# arduino_SCH.net
KiCad netlist of a schematic drawn in Altium Designer
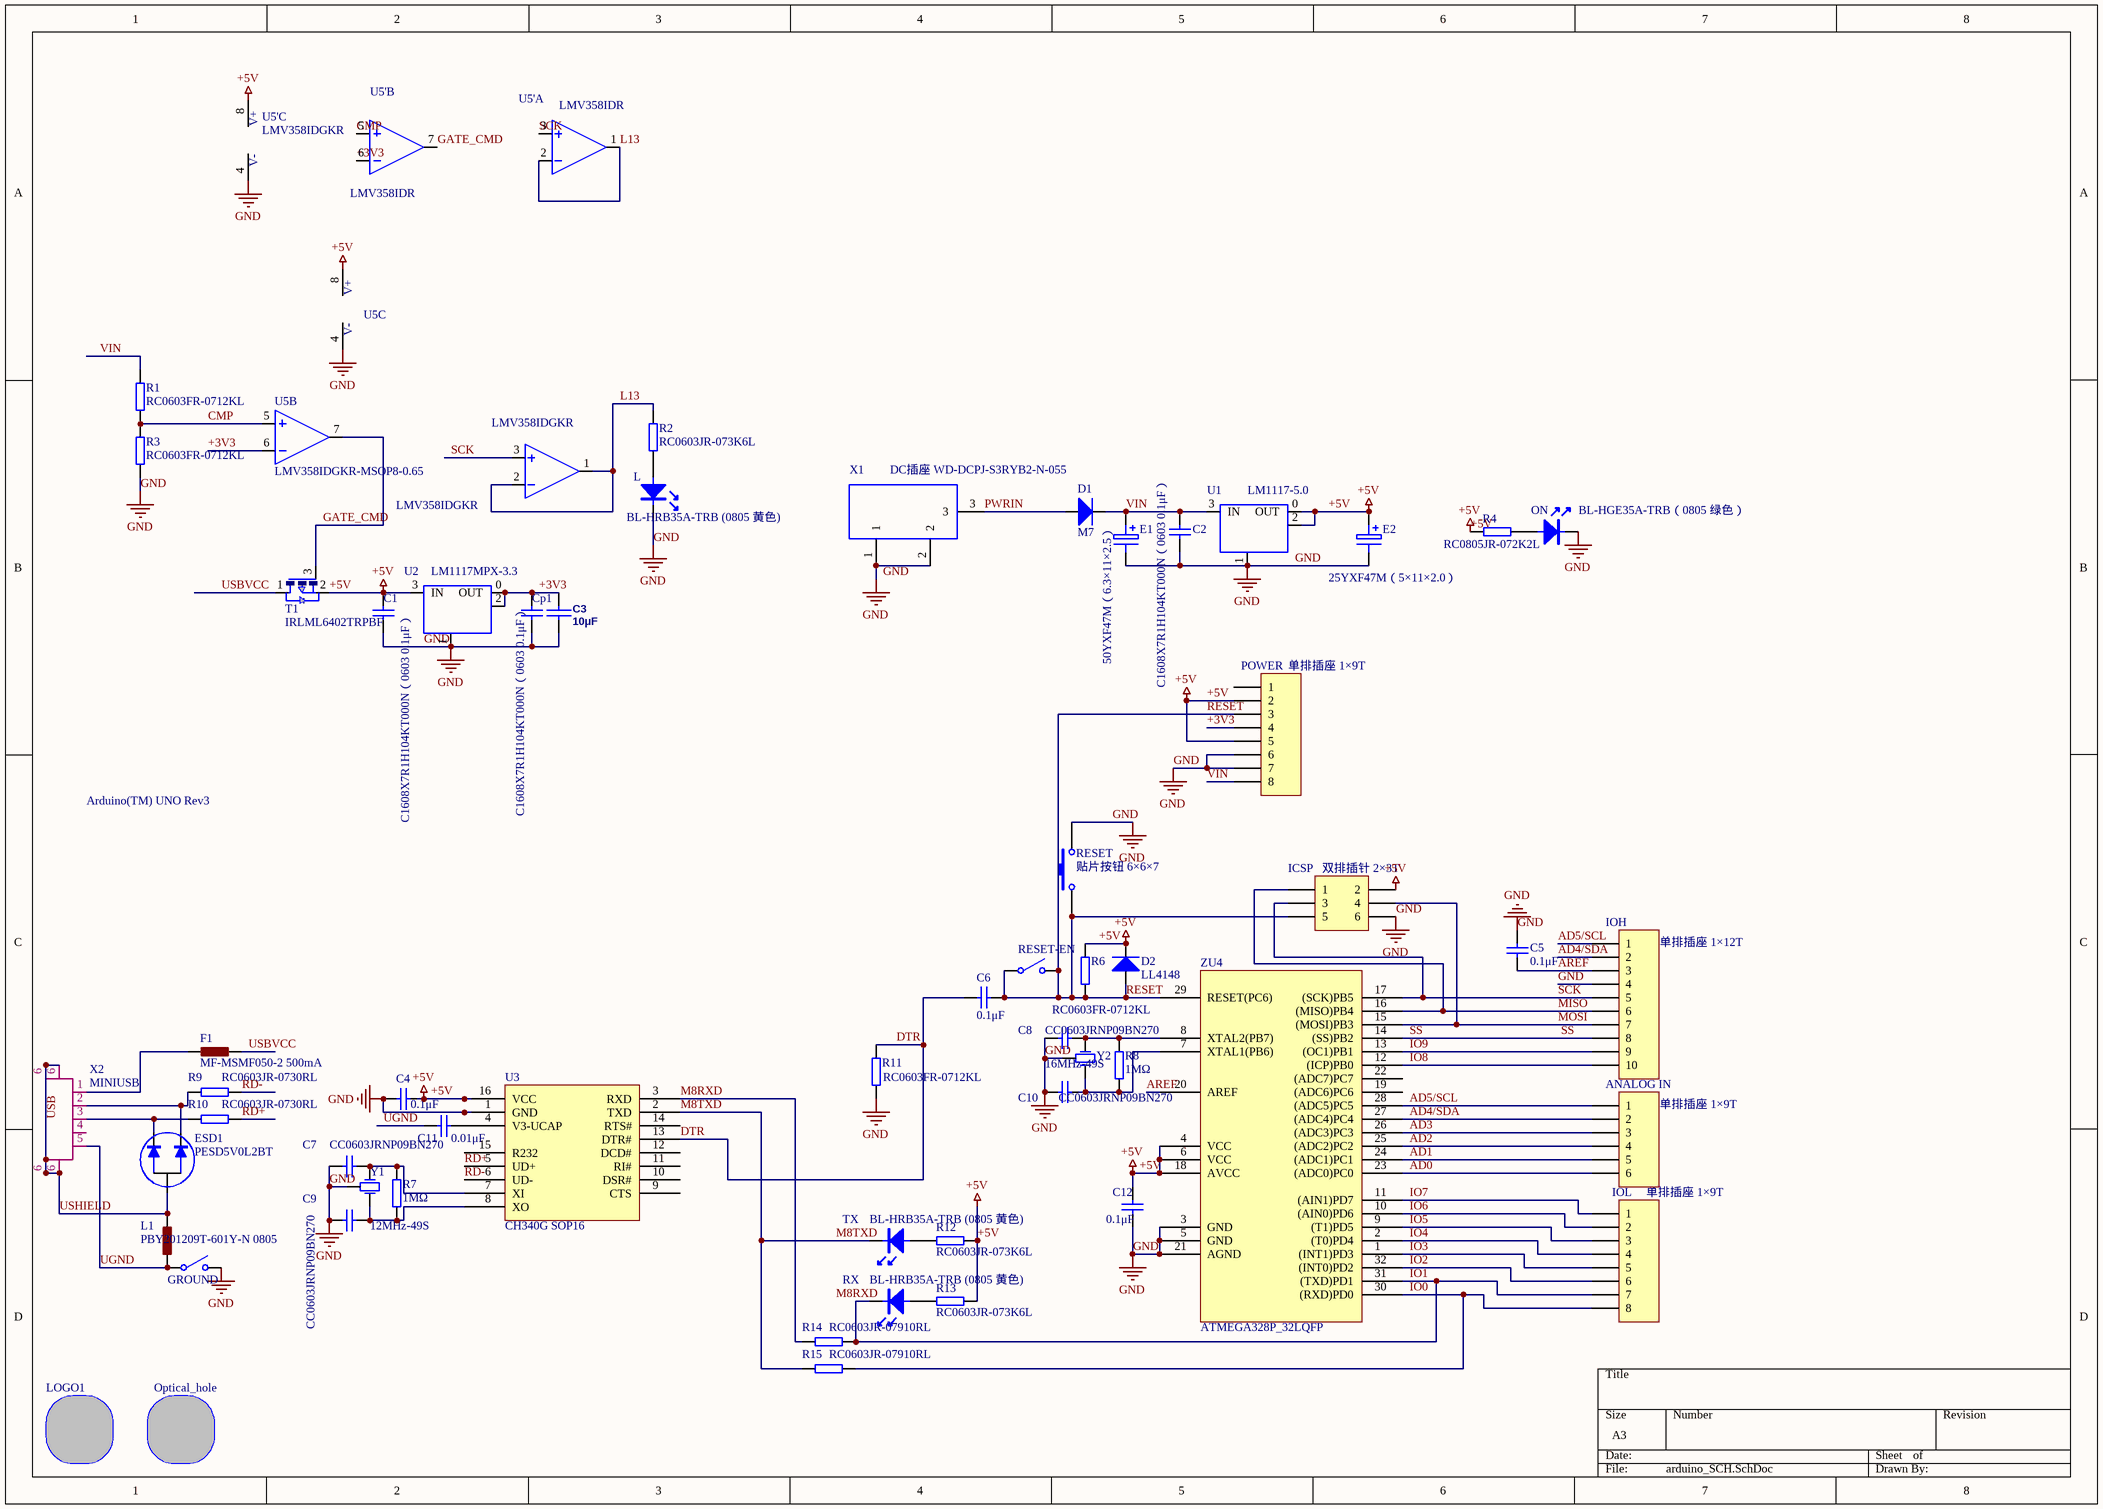
[diagram p0: arduino_SCH.SchDoc]

(export (version "E")
  (design (tool "Eeschema 10.0.6"))
  (components
    (comp (ref "ANALOG IN")
      (value "单排插座 1×9T")
      (footprint "HDR1X6Z")
      (description "Header, 6-Pin")
      (fields (field (name "PUBLISHER") "Altium Limited"))
      (libsource (lib "Miscellaneous Connectors") (part "Header 6"))
    )
    (comp (ref "C1")
      (value "C1608X7R1H104KT000N（0603 0.1μF）")
      (footprint "0603C")
      (description "Capacitor")
      (fields (field (name "PUBLISHER") "Altium Limited"))
      (libsource (lib "*") (part "Cap"))
    )
    (comp (ref "C2")
      (value "C1608X7R1H104KT000N（0603 0.1μF）")
      (footprint "0603C")
      (description "Capacitor")
      (fields (field (name "PUBLISHER") "Altium Limited"))
      (libsource (lib "Miscellaneous Devices") (part "Cap"))
    )
    (comp (ref "C3")
      (value "10μF")
      (footprint "1206C")
      (description "Capacitor")
      (libsource (lib "*") (part "CAP"))
    )
    (comp (ref "C4")
      (value "0.1μF")
      (footprint "0603C")
      (description "Capacitor")
      (fields (field (name "PUBLISHER") "Altium Limited"))
      (libsource (lib "Miscellaneous Devices") (part "Cap"))
    )
    (comp (ref "C5")
      (value "0.1μF")
      (footprint "0603C")
      (description "Capacitor")
      (fields (field (name "PUBLISHER") "Altium Limited"))
      (libsource (lib "Miscellaneous Devices") (part "Cap"))
    )
    (comp (ref "C6")
      (value "0.1μF")
      (footprint "0603C")
      (description "Capacitor")
      (fields (field (name "PUBLISHER") "Altium Limited"))
      (libsource (lib "Miscellaneous Devices") (part "Cap"))
    )
    (comp (ref "C7")
      (value "CC0603JRNP09BN270")
      (footprint "0603C")
      (description "Capacitor")
      (fields (field (name "PUBLISHER") "Altium Limited"))
      (libsource (lib "Miscellaneous Devices") (part "Cap"))
    )
    (comp (ref "C8")
      (value "CC0603JRNP09BN270")
      (footprint "0603C")
      (description "Capacitor")
      (fields (field (name "PUBLISHER") "Altium Limited"))
      (libsource (lib "Miscellaneous Devices") (part "Cap"))
    )
    (comp (ref "C9")
      (value "CC0603JRNP09BN270")
      (footprint "0603C")
      (description "Capacitor")
      (fields (field (name "PUBLISHER") "Altium Limited"))
      (libsource (lib "Miscellaneous Devices") (part "Cap"))
    )
    (comp (ref "C10")
      (value "CC0603JRNP09BN270")
      (footprint "0603C")
      (description "Capacitor")
      (fields (field (name "PUBLISHER") "Altium Limited"))
      (libsource (lib "Miscellaneous Devices") (part "Cap"))
    )
    (comp (ref "C11")
      (value "0.01μF")
      (footprint "0603C")
      (description "Capacitor")
      (fields (field (name "PUBLISHER") "Altium Limited"))
      (libsource (lib "Miscellaneous Devices") (part "Cap"))
    )
    (comp (ref "C12")
      (value "0.1μF")
      (footprint "0603C")
      (description "Capacitor")
      (fields (field (name "PUBLISHER") "Altium Limited"))
      (libsource (lib "Miscellaneous Devices") (part "Cap"))
    )
    (comp (ref "Cp1")
      (value "C1608X7R1H104KT000N（0603 0.1μF）")
      (footprint "0603C")
      (description "Capacitor")
      (fields (field (name "PUBLISHER") "Altium Limited"))
      (libsource (lib "*") (part "Cap"))
    )
    (comp (ref "D1")
      (value "M7")
      (footprint "M7")
      (description "D")
      (libsource (lib "Miscellaneous Devices") (part "M7"))
    )
    (comp (ref "D2")
      (value "LL4148")
      (footprint "D1206")
      (description "D")
      (libsource (lib "Miscellaneous Devices") (part "M7"))
    )
    (comp (ref "E1")
      (value "50YXF47M（6.3×11×2.5）")
      (footprint "RB 6.3×11×2.5")
      (libsource (lib "Miscellaneous Devices") (part "E"))
    )
    (comp (ref "E2")
      (value "25YXF47M（5×11×2.0）")
      (footprint "RB 6.3×11×2.5")
      (libsource (lib "Miscellaneous Devices") (part "E"))
    )
    (comp (ref "ESD1")
      (value "PESD5V0L2BT")
      (footprint "SOT-23")
      (libsource (lib "Miscellaneous Devices") (part "ESD1"))
    )
    (comp (ref "F1")
      (value "MF-MSMF050-2 500mA")
      (footprint "L1206")
      (description "BLM21")
      (libsource (lib "") (part "L_1"))
    )
    (comp (ref "GROUND")
      (value "~")
      (footprint "0101")
      (description "Single-Pole, Single-Throw Switch")
      (fields (field (name "PUBLISHER") "Altium Limited"))
      (libsource (lib "Miscellaneous Devices") (part "SW-SPST"))
    )
    (comp (ref "ICSP")
      (value "双排插针 2×3T")
      (footprint "HDR2X3")
      (description "Header, 3-Pin, Dual row")
      (fields (field (name "PUBLISHER") "Altium Limited"))
      (libsource (lib "Miscellaneous Connectors") (part "Header 3X2"))
    )
    (comp (ref "IOH")
      (value "单排插座 1×12T")
      (footprint "HDR1X10Z")
      (description "Header, 10-Pin")
      (fields (field (name "PUBLISHER") "Altium Limited"))
      (libsource (lib "Miscellaneous Connectors") (part "Header 10"))
    )
    (comp (ref "IOL")
      (value "单排插座 1×9T")
      (footprint "HDR1X8Z")
      (description "Header, 8-Pin")
      (fields (field (name "PUBLISHER") "Altium Limited"))
      (libsource (lib "Miscellaneous Connectors") (part "Header 8"))
    )
    (comp (ref "L")
      (value "BL-HRB35A-TRB (0805 黄色)")
      (footprint "LED0805-Y")
      (libsource (lib "Miscellaneous Devices") (part "LED"))
    )
    (comp (ref "L1")
      (value "PBY201209T-601Y-N 0805")
      (footprint "L0805")
      (description "BLM21")
      (libsource (lib "Miscellaneous Devices") (part "L"))
    )
    (comp (ref "LOGO1")
      (value "LOGO")
      (footprint "USB_LOGO")
      (libsource (lib "Miscellaneous Connectors") (part "LOGO"))
    )
    (comp (ref "ON")
      (value "BL-HGE35A-TRB（0805 绿色）")
      (footprint "LED0805-R")
      (libsource (lib "Miscellaneous Devices") (part "LED"))
    )
    (comp (ref "POWER")
      (value "单排插座 1×9T")
      (footprint "HDR1X8Z")
      (description "Header, 8-Pin")
      (fields (field (name "PUBLISHER") "Altium Limited"))
      (libsource (lib "Miscellaneous Connectors") (part "Header 8"))
    )
    (comp (ref "R1")
      (value "RC0603FR-0712KL")
      (footprint "0603R")
      (description "Resistor")
      (libsource (lib "Miscellaneous Devices") (part "R"))
    )
    (comp (ref "R2")
      (value "RC0603JR-073K6L")
      (footprint "0603R")
      (description "Resistor")
      (libsource (lib "Miscellaneous Devices") (part "R"))
    )
    (comp (ref "R3")
      (value "RC0603FR-0712KL")
      (footprint "0603R")
      (description "Resistor")
      (libsource (lib "Miscellaneous Devices") (part "R"))
    )
    (comp (ref "R4")
      (value "RC0805JR-072K2L")
      (footprint "0805/R")
      (description "Resistor")
      (libsource (lib "Miscellaneous Devices") (part "R"))
    )
    (comp (ref "R6")
      (value "RC0603FR-0712KL")
      (footprint "0603R")
      (description "Resistor")
      (libsource (lib "Miscellaneous Devices") (part "R"))
    )
    (comp (ref "R7")
      (value "1MΩ")
      (footprint "0603R")
      (description "Resistor")
      (libsource (lib "Miscellaneous Devices") (part "R"))
    )
    (comp (ref "R8")
      (value "1MΩ")
      (footprint "0603R")
      (description "Resistor")
      (libsource (lib "Miscellaneous Devices") (part "R"))
    )
    (comp (ref "R9")
      (value "RC0603JR-0730RL")
      (footprint "0603R")
      (description "Resistor")
      (libsource (lib "Miscellaneous Devices") (part "R"))
    )
    (comp (ref "R10")
      (value "RC0603JR-0730RL")
      (footprint "0603R")
      (description "Resistor")
      (libsource (lib "Miscellaneous Devices") (part "R"))
    )
    (comp (ref "R11")
      (value "RC0603FR-0712KL")
      (footprint "0603R")
      (description "Resistor")
      (libsource (lib "Miscellaneous Devices") (part "R"))
    )
    (comp (ref "R12")
      (value "RC0603JR-073K6L")
      (footprint "0603R")
      (description "Resistor")
      (libsource (lib "Miscellaneous Devices") (part "R"))
    )
    (comp (ref "R13")
      (value "RC0603JR-073K6L")
      (footprint "0603R")
      (description "Resistor")
      (libsource (lib "Miscellaneous Devices") (part "R"))
    )
    (comp (ref "R14")
      (value "RC0603JR-07910RL")
      (footprint "0603R")
      (description "Resistor")
      (libsource (lib "Miscellaneous Devices") (part "R"))
    )
    (comp (ref "R15")
      (value "RC0603JR-07910RL")
      (footprint "0603R")
      (description "Resistor")
      (libsource (lib "Miscellaneous Devices") (part "R"))
    )
    (comp (ref "RESET")
      (value "贴片按钮 6×6×7")
      (footprint "按钮/SO")
      (description "Switch")
      (fields (field (name "PUBLISHER") "Altium Limited"))
      (libsource (lib "Miscellaneous Devices") (part "SW-PB"))
    )
    (comp (ref "RESET-EN")
      (value "~")
      (footprint "0101")
      (description "Single-Pole, Single-Throw Switch")
      (fields (field (name "PUBLISHER") "Altium Limited"))
      (libsource (lib "Miscellaneous Devices") (part "SW-SPST"))
    )
    (comp (ref "RX")
      (value "BL-HRB35A-TRB (0805 黄色)")
      (footprint "LED0805-Y")
      (libsource (lib "Miscellaneous Devices") (part "LED"))
    )
    (comp (ref "T1")
      (value "IRLML6402TRPBF")
      (footprint "MOSFET")
      (libsource (lib "Miscellaneous Devices") (part "PMOSSOT23"))
    )
    (comp (ref "TX")
      (value "BL-HRB35A-TRB (0805 黄色)")
      (footprint "LED0805-Y")
      (libsource (lib "Miscellaneous Devices") (part "LED"))
    )
    (comp (ref "U$1")
      (value "Optical_hole")
      (footprint "MARK")
      (libsource (lib "Miscellaneous Connectors") (part "LOGO"))
    )
    (comp (ref "U1")
      (value "LM1117-5.0")
      (footprint "SOT223")
      (libsource (lib "Miscellaneous Devices") (part "LM1117"))
    )
    (comp (ref "U2")
      (value "LM1117MPX-3.3")
      (footprint "SOT223")
      (libsource (lib "Miscellaneous Devices") (part "LM1117"))
    )
    (comp (ref "U3")
      (value "CH340G SOP16")
      (footprint "SO-16")
      (libsource (lib "Miscellaneous Devices") (part "CH340G"))
    )
    (comp (ref "U5")
      (value "LMV358IDGKR-MSOP8-0.65")
      (footprint "MSOP8-0.65")
      (libsource (lib "Miscellaneous Devices") (part "LMV358MMX"))
    )
    (comp (ref "U5'")
      (value "LMV358IDR")
      (footprint "so-8")
      (libsource (lib "Miscellaneous Devices") (part "LMV358MMX"))
    )
    (comp (ref "X1")
      (value "DC插座 WD-DCPJ-S3RYB2-N-055")
      (footprint "DC_IN")
      (description "POWERSUPPLY_DC21MMX")
      (libsource (lib "Miscellaneous Connectors") (part "DC_IN"))
    )
    (comp (ref "X2")
      (value "MINIUSB")
      (footprint "USB-MINI3")
      (description "USB")
      (libsource (lib "Miscellaneous Connectors") (part "USB-B_MINI"))
    )
    (comp (ref "Y1")
      (value "12MHz-49S")
      (footprint "XTAL-49S")
      (description "3pXTAL")
      (libsource (lib "Miscellaneous Devices") (part "XTAL1"))
    )
    (comp (ref "Y2")
      (value "16MHz-49S")
      (footprint "XTAL-49S")
      (description "3pXTAL")
      (libsource (lib "Miscellaneous Devices") (part "XTAL1"))
    )
    (comp (ref "ZU4")
      (value "ATMEGA328P_32LQFP")
      (footprint "LQFP32")
      (description "Arduino ATMEGA328P")
      (libsource (lib "Miscellaneous Devices") (part "ATMEGA328P_32LQFP"))
    )
  )
  (nets
    (net (code "1") (name "+5V") (class "Default")
      (node (ref "C1") (pin "1") (pinfunction "1_1") (pintype "passive"))
      (node (ref "C12") (pin "2") (pinfunction "2_2") (pintype "passive"))
      (node (ref "C4") (pin "2") (pinfunction "2_2") (pintype "passive"))
      (node (ref "D2") (pin "K") (pinfunction "K_K") (pintype "passive"))
      (node (ref "E2") (pin "1") (pintype "passive"))
      (node (ref "ICSP") (pin "2") (pinfunction "2_2") (pintype "passive"))
      (node (ref "POWER") (pin "2") (pinfunction "2_2") (pintype "passive"))
      (node (ref "POWER") (pin "5") (pinfunction "5_5") (pintype "passive"))
      (node (ref "R12") (pin "1") (pintype "passive"))
      (node (ref "R13") (pin "1") (pintype "passive"))
      (node (ref "R4") (pin "2") (pintype "passive"))
      (node (ref "R6") (pin "1") (pintype "passive"))
      (node (ref "T1") (pin "2") (pinfunction "S_2") (pintype "passive"))
      (node (ref "U1") (pin "0") (pinfunction "OUT_0") (pintype "passive"))
      (node (ref "U1") (pin "2") (pinfunction "OUT@1_2") (pintype "passive"))
      (node (ref "U2") (pin "3") (pinfunction "IN_3") (pintype "passive"))
      (node (ref "U3") (pin "16") (pinfunction "VCC_16") (pintype "passive"))
      (node (ref "U5") (pin "8") (pinfunction "V+_8") (pintype "passive"))
      (node (ref "U5'") (pin "8") (pinfunction "V+_8") (pintype "passive"))
      (node (ref "ZU4") (pin "18") (pinfunction "AVCC_18") (pintype "passive"))
      (node (ref "ZU4") (pin "4") (pinfunction "VCC_4") (pintype "passive"))
      (node (ref "ZU4") (pin "6") (pinfunction "VCC_6") (pintype "passive"))
    )
    (net (code "2") (name "/+3V3") (class "Default")
      (node (ref "C3") (pin "2") (pinfunction "2_2") (pintype "passive"))
      (node (ref "Cp1") (pin "1") (pinfunction "1_1") (pintype "passive"))
      (node (ref "POWER") (pin "4") (pinfunction "4_4") (pintype "passive"))
      (node (ref "U2") (pin "0") (pinfunction "OUT_0") (pintype "passive"))
      (node (ref "U2") (pin "2") (pinfunction "OUT@1_2") (pintype "passive"))
      (node (ref "U5") (pin "6") (pinfunction "-IN_6") (pintype "passive"))
      (node (ref "U5'") (pin "6") (pinfunction "-IN_6") (pintype "passive"))
    )
    (net (code "3") (name "/AD0") (class "Default")
      (node (ref "ANALOG IN") (pin "6") (pinfunction "6_6") (pintype "passive"))
      (node (ref "ZU4") (pin "23") (pinfunction "(ADC0)PC0_23") (pintype "passive"))
    )
    (net (code "4") (name "/AD1") (class "Default")
      (node (ref "ANALOG IN") (pin "5") (pinfunction "5_5") (pintype "passive"))
      (node (ref "ZU4") (pin "24") (pinfunction "(ADC1)PC1_24") (pintype "passive"))
    )
    (net (code "5") (name "/AD2") (class "Default")
      (node (ref "ANALOG IN") (pin "4") (pinfunction "4_4") (pintype "passive"))
      (node (ref "ZU4") (pin "25") (pinfunction "(ADC2)PC2_25") (pintype "passive"))
    )
    (net (code "6") (name "/AD3") (class "Default")
      (node (ref "ANALOG IN") (pin "3") (pinfunction "3_3") (pintype "passive"))
      (node (ref "ZU4") (pin "26") (pinfunction "(ADC3)PC3_26") (pintype "passive"))
    )
    (net (code "7") (name "/AD4{slash}SDA") (class "Default")
      (node (ref "ANALOG IN") (pin "2") (pinfunction "2_2") (pintype "passive"))
      (node (ref "IOH") (pin "2") (pinfunction "2_2") (pintype "passive"))
      (node (ref "ZU4") (pin "27") (pinfunction "(ADC4)PC4_27") (pintype "passive"))
    )
    (net (code "8") (name "/AD5{slash}SCL") (class "Default")
      (node (ref "ANALOG IN") (pin "1") (pinfunction "1_1") (pintype "passive"))
      (node (ref "IOH") (pin "1") (pinfunction "1_1") (pintype "passive"))
      (node (ref "ZU4") (pin "28") (pinfunction "(ADC5)PC5_28") (pintype "passive"))
    )
    (net (code "9") (name "/AREF") (class "Default")
      (node (ref "C5") (pin "1") (pinfunction "1_1") (pintype "passive"))
      (node (ref "IOH") (pin "3") (pinfunction "3_3") (pintype "passive"))
      (node (ref "ZU4") (pin "20") (pinfunction "AREF_20") (pintype "passive"))
    )
    (net (code "10") (name "/CMP") (class "Default")
      (node (ref "R1") (pin "2") (pintype "passive"))
      (node (ref "R3") (pin "1") (pintype "passive"))
      (node (ref "U5") (pin "5") (pinfunction "+IN_5") (pintype "passive"))
      (node (ref "U5'") (pin "5") (pinfunction "+IN_5") (pintype "passive"))
    )
    (net (code "11") (name "/DTR") (class "Default")
      (node (ref "C6") (pin "1") (pinfunction "1_1") (pintype "passive"))
      (node (ref "R11") (pin "1") (pintype "passive"))
      (node (ref "U3") (pin "13") (pinfunction "DTR#_13") (pintype "passive"))
    )
    (net (code "12") (name "/GATE_CMD") (class "Default")
      (node (ref "T1") (pin "3") (pinfunction "G_3") (pintype "passive"))
      (node (ref "U5") (pin "7") (pinfunction "OUT_7") (pintype "passive"))
      (node (ref "U5'") (pin "7") (pinfunction "OUT_7") (pintype "passive"))
    )
    (net (code "13") (name "/IO0") (class "Default")
      (node (ref "IOL") (pin "8") (pinfunction "8_8") (pintype "passive"))
      (node (ref "R15") (pin "1") (pintype "passive"))
      (node (ref "ZU4") (pin "30") (pinfunction "(RXD)PD0_30") (pintype "passive"))
    )
    (net (code "14") (name "/IO1") (class "Default")
      (node (ref "IOL") (pin "7") (pinfunction "7_7") (pintype "passive"))
      (node (ref "R14") (pin "1") (pintype "passive"))
      (node (ref "RX") (pin "K") (pintype "passive"))
      (node (ref "ZU4") (pin "31") (pinfunction "(TXD)PD1_31") (pintype "passive"))
    )
    (net (code "15") (name "/IO2") (class "Default")
      (node (ref "IOL") (pin "6") (pinfunction "6_6") (pintype "passive"))
      (node (ref "ZU4") (pin "32") (pinfunction "(INT0)PD2_32") (pintype "passive"))
    )
    (net (code "16") (name "/IO3") (class "Default")
      (node (ref "IOL") (pin "5") (pinfunction "5_5") (pintype "passive"))
      (node (ref "ZU4") (pin "1") (pinfunction "(INT1)PD3_1") (pintype "passive"))
    )
    (net (code "17") (name "/IO4") (class "Default")
      (node (ref "IOL") (pin "4") (pinfunction "4_4") (pintype "passive"))
      (node (ref "ZU4") (pin "2") (pinfunction "(T0)PD4_2") (pintype "passive"))
    )
    (net (code "18") (name "/IO5") (class "Default")
      (node (ref "IOL") (pin "3") (pinfunction "3_3") (pintype "passive"))
      (node (ref "ZU4") (pin "9") (pinfunction "(T1)PD5_9") (pintype "passive"))
    )
    (net (code "19") (name "/IO6") (class "Default")
      (node (ref "IOL") (pin "2") (pinfunction "2_2") (pintype "passive"))
      (node (ref "ZU4") (pin "10") (pinfunction "(AIN0)PD6_10") (pintype "passive"))
    )
    (net (code "20") (name "/IO7") (class "Default")
      (node (ref "IOL") (pin "1") (pinfunction "1_1") (pintype "passive"))
      (node (ref "ZU4") (pin "11") (pinfunction "(AIN1)PD7_11") (pintype "passive"))
    )
    (net (code "21") (name "/IO8") (class "Default")
      (node (ref "IOH") (pin "10") (pinfunction "10_10") (pintype "passive"))
      (node (ref "ZU4") (pin "12") (pinfunction "(ICP)PB0_12") (pintype "passive"))
    )
    (net (code "22") (name "/IO9") (class "Default")
      (node (ref "IOH") (pin "9") (pinfunction "9_9") (pintype "passive"))
      (node (ref "ZU4") (pin "13") (pinfunction "(OC1)PB1_13") (pintype "passive"))
    )
    (net (code "23") (name "/L13") (class "Default")
      (node (ref "R2") (pin "1") (pintype "passive"))
      (node (ref "U5") (pin "1") (pinfunction "OUT_1") (pintype "passive"))
      (node (ref "U5") (pin "2") (pinfunction "-IN_2") (pintype "passive"))
      (node (ref "U5'") (pin "1") (pinfunction "OUT_1") (pintype "passive"))
      (node (ref "U5'") (pin "2") (pinfunction "-IN_2") (pintype "passive"))
    )
    (net (code "24") (name "/M8RXD") (class "Default")
      (node (ref "R14") (pin "2") (pintype "passive"))
      (node (ref "U3") (pin "3") (pinfunction "RXD_3") (pintype "passive"))
    )
    (net (code "25") (name "/M8TXD") (class "Default")
      (node (ref "R15") (pin "2") (pintype "passive"))
      (node (ref "TX") (pin "K") (pintype "passive"))
      (node (ref "U3") (pin "2") (pinfunction "TXD_2") (pintype "passive"))
    )
    (net (code "26") (name "/MISO") (class "Default")
      (node (ref "ICSP") (pin "1") (pinfunction "1_1") (pintype "passive"))
      (node (ref "IOH") (pin "6") (pinfunction "6_6") (pintype "passive"))
      (node (ref "ZU4") (pin "16") (pinfunction "(MISO)PB4_16") (pintype "passive"))
    )
    (net (code "27") (name "/MOSI") (class "Default")
      (node (ref "ICSP") (pin "4") (pinfunction "4_4") (pintype "passive"))
      (node (ref "IOH") (pin "7") (pinfunction "7_7") (pintype "passive"))
      (node (ref "ZU4") (pin "15") (pinfunction "(MOSI)PB3_15") (pintype "passive"))
    )
    (net (code "28") (name "/PWRIN") (class "Default")
      (node (ref "D1") (pin "A") (pinfunction "A_A") (pintype "passive"))
      (node (ref "X1") (pin "3") (pinfunction "3_3") (pintype "passive"))
    )
    (net (code "29") (name "/RD+") (class "Default")
      (node (ref "R10") (pin "1") (pintype "passive"))
      (node (ref "U3") (pin "5") (pinfunction "UD+_5") (pintype "passive"))
    )
    (net (code "30") (name "/RD-") (class "Default")
      (node (ref "R9") (pin "1") (pintype "passive"))
      (node (ref "U3") (pin "6") (pinfunction "UD-_6") (pintype "passive"))
    )
    (net (code "31") (name "/RESET") (class "Default")
      (node (ref "C6") (pin "2") (pinfunction "2_2") (pintype "passive"))
      (node (ref "D2") (pin "A") (pinfunction "A_A") (pintype "passive"))
      (node (ref "ICSP") (pin "5") (pinfunction "5_5") (pintype "passive"))
      (node (ref "POWER") (pin "3") (pinfunction "3_3") (pintype "passive"))
      (node (ref "R6") (pin "2") (pintype "passive"))
      (node (ref "RESET") (pin "1") (pinfunction "1_1") (pintype "passive"))
      (node (ref "RESET-EN") (pin "1") (pinfunction "COMMON_1") (pintype "passive"))
      (node (ref "RESET-EN") (pin "2") (pinfunction "NO_2") (pintype "passive"))
      (node (ref "ZU4") (pin "29") (pinfunction "RESET(PC6)_29") (pintype "passive"))
    )
    (net (code "32") (name "/SCK") (class "Default")
      (node (ref "ICSP") (pin "3") (pinfunction "3_3") (pintype "passive"))
      (node (ref "IOH") (pin "5") (pinfunction "5_5") (pintype "passive"))
      (node (ref "U5") (pin "3") (pinfunction "+IN_3") (pintype "passive"))
      (node (ref "U5'") (pin "3") (pinfunction "+IN_3") (pintype "passive"))
      (node (ref "ZU4") (pin "17") (pinfunction "(SCK)PB5_17") (pintype "passive"))
    )
    (net (code "33") (name "/SS") (class "Default")
      (node (ref "IOH") (pin "8") (pinfunction "8_8") (pintype "passive"))
      (node (ref "ZU4") (pin "14") (pinfunction "(SS)PB2_14") (pintype "passive"))
    )
    (net (code "34") (name "/UGND") (class "Default")
      (node (ref "C11") (pin "2") (pinfunction "2_2") (pintype "passive"))
      (node (ref "GROUND") (pin "1") (pinfunction "COMMON_1") (pintype "passive"))
      (node (ref "L1") (pin "2") (pintype "passive"))
      (node (ref "X2") (pin "5") (pintype "passive"))
    )
    (net (code "35") (name "/USBVCC") (class "Default")
      (node (ref "F1") (pin "1") (pintype "passive"))
      (node (ref "T1") (pin "1") (pinfunction "D_1") (pintype "passive"))
    )
    (net (code "36") (name "/USHIELD") (class "Default")
      (node (ref "ESD1") (pin "3") (pinfunction "3_3") (pintype "passive"))
      (node (ref "L1") (pin "1") (pintype "passive"))
      (node (ref "X2") (pin "6") (pintype "passive"))
    )
    (net (code "37") (name "/VIN") (class "Default")
      (node (ref "C2") (pin "2") (pinfunction "2_2") (pintype "passive"))
      (node (ref "D1") (pin "K") (pinfunction "K_K") (pintype "passive"))
      (node (ref "E1") (pin "1") (pintype "passive"))
      (node (ref "POWER") (pin "8") (pinfunction "8_8") (pintype "passive"))
      (node (ref "R1") (pin "1") (pintype "passive"))
      (node (ref "U1") (pin "3") (pinfunction "IN_3") (pintype "passive"))
    )
    (net (code "38") (name "GND") (class "Default")
      (node (ref "C1") (pin "2") (pinfunction "2_2") (pintype "passive"))
      (node (ref "C10") (pin "1") (pinfunction "1_1") (pintype "passive"))
      (node (ref "C12") (pin "1") (pinfunction "1_1") (pintype "passive"))
      (node (ref "C2") (pin "1") (pinfunction "1_1") (pintype "passive"))
      (node (ref "C3") (pin "1") (pinfunction "1_1") (pintype "passive"))
      (node (ref "C4") (pin "1") (pinfunction "1_1") (pintype "passive"))
      (node (ref "C5") (pin "2") (pinfunction "2_2") (pintype "passive"))
      (node (ref "C7") (pin "1") (pinfunction "1_1") (pintype "passive"))
      (node (ref "C8") (pin "1") (pinfunction "1_1") (pintype "passive"))
      (node (ref "C9") (pin "1") (pinfunction "1_1") (pintype "passive"))
      (node (ref "Cp1") (pin "2") (pinfunction "2_2") (pintype "passive"))
      (node (ref "E1") (pin "2") (pintype "passive"))
      (node (ref "E2") (pin "2") (pintype "passive"))
      (node (ref "GROUND") (pin "2") (pinfunction "NO_2") (pintype "passive"))
      (node (ref "ICSP") (pin "6") (pinfunction "6_6") (pintype "passive"))
      (node (ref "IOH") (pin "4") (pinfunction "4_4") (pintype "passive"))
      (node (ref "L") (pin "K") (pintype "passive"))
      (node (ref "ON") (pin "K") (pintype "passive"))
      (node (ref "POWER") (pin "6") (pinfunction "6_6") (pintype "passive"))
      (node (ref "POWER") (pin "7") (pinfunction "7_7") (pintype "passive"))
      (node (ref "R11") (pin "2") (pintype "passive"))
      (node (ref "R3") (pin "2") (pintype "passive"))
      (node (ref "RESET") (pin "2") (pinfunction "2_2") (pintype "passive"))
      (node (ref "U1") (pin "1") (pinfunction "GND/ADJ_1") (pintype "passive"))
      (node (ref "U2") (pin "1") (pinfunction "GND/ADJ_1") (pintype "passive"))
      (node (ref "U3") (pin "1") (pinfunction "GND_1") (pintype "passive"))
      (node (ref "U5") (pin "4") (pinfunction "V-_4") (pintype "passive"))
      (node (ref "U5'") (pin "4") (pinfunction "V-_4") (pintype "passive"))
      (node (ref "X1") (pin "1") (pinfunction "1_1") (pintype "passive"))
      (node (ref "X1") (pin "2") (pinfunction "2_2") (pintype "passive"))
      (node (ref "Y1") (pin "3") (pinfunction "3_3") (pintype "passive"))
      (node (ref "Y2") (pin "3") (pinfunction "3_3") (pintype "passive"))
      (node (ref "ZU4") (pin "21") (pinfunction "AGND_21") (pintype "passive"))
      (node (ref "ZU4") (pin "3") (pinfunction "GND_3") (pintype "passive"))
      (node (ref "ZU4") (pin "5") (pinfunction "GND_5") (pintype "passive"))
    )
    (net (code "39") (name "Net-(ESD1-Pad1)") (class "Default")
      (node (ref "ESD1") (pin "1") (pinfunction "1_1") (pintype "passive"))
      (node (ref "R10") (pin "2") (pintype "passive"))
      (node (ref "X2") (pin "3") (pintype "passive"))
    )
    (net (code "40") (name "Net-(ESD1-Pad2)") (class "Default")
      (node (ref "ESD1") (pin "2") (pinfunction "2_2") (pintype "passive"))
      (node (ref "R9") (pin "2") (pintype "passive"))
      (node (ref "X2") (pin "2") (pintype "passive"))
    )
    (net (code "41") (name "Net-(F1-Pad2)") (class "Default")
      (node (ref "F1") (pin "2") (pintype "passive"))
      (node (ref "X2") (pin "1") (pintype "passive"))
    )
    (net (code "42") (name "Net-(L-PadA)") (class "Default")
      (node (ref "L") (pin "A") (pintype "passive"))
      (node (ref "R2") (pin "2") (pintype "passive"))
    )
    (net (code "43") (name "Net-(ON-PadA)") (class "Default")
      (node (ref "ON") (pin "A") (pintype "passive"))
      (node (ref "R4") (pin "1") (pintype "passive"))
    )
    (net (code "44") (name "Net-(R12-Pad2)") (class "Default")
      (node (ref "R12") (pin "2") (pintype "passive"))
      (node (ref "TX") (pin "A") (pintype "passive"))
    )
    (net (code "45") (name "Net-(R13-Pad2)") (class "Default")
      (node (ref "R13") (pin "2") (pintype "passive"))
      (node (ref "RX") (pin "A") (pintype "passive"))
    )
    (net (code "46") (name "Net-(U3-V3-UCAP)") (class "Default")
      (node (ref "C11") (pin "1") (pinfunction "1_1") (pintype "passive"))
      (node (ref "U3") (pin "4") (pinfunction "V3-UCAP_4") (pintype "passive"))
    )
    (net (code "47") (name "Net-(U3-XI)") (class "Default")
      (node (ref "C7") (pin "2") (pinfunction "2_2") (pintype "passive"))
      (node (ref "R7") (pin "1") (pintype "passive"))
      (node (ref "U3") (pin "7") (pinfunction "XI_7") (pintype "passive"))
      (node (ref "Y1") (pin "1") (pinfunction "OSC1_1") (pintype "passive"))
    )
    (net (code "48") (name "Net-(U3-XO)") (class "Default")
      (node (ref "C9") (pin "2") (pinfunction "2_2") (pintype "passive"))
      (node (ref "R7") (pin "2") (pintype "passive"))
      (node (ref "U3") (pin "8") (pinfunction "XO_8") (pintype "passive"))
      (node (ref "Y1") (pin "2") (pinfunction "OSC2_2") (pintype "passive"))
    )
    (net (code "49") (name "Net-(Y2-OSC1)") (class "Default")
      (node (ref "C8") (pin "2") (pinfunction "2_2") (pintype "passive"))
      (node (ref "R8") (pin "1") (pintype "passive"))
      (node (ref "Y2") (pin "1") (pinfunction "OSC1_1") (pintype "passive"))
      (node (ref "ZU4") (pin "8") (pinfunction "XTAL2(PB7)_8") (pintype "passive"))
    )
    (net (code "50") (name "Net-(Y2-OSC2)") (class "Default")
      (node (ref "C10") (pin "2") (pinfunction "2_2") (pintype "passive"))
      (node (ref "R8") (pin "2") (pintype "passive"))
      (node (ref "Y2") (pin "2") (pinfunction "OSC2_2") (pintype "passive"))
      (node (ref "ZU4") (pin "7") (pinfunction "XTAL1(PB6)_7") (pintype "passive"))
    )
    (net (code "51") (name "unconnected-(POWER-Pad1)") (class "Default")
      (node (ref "POWER") (pin "1") (pinfunction "1_1") (pintype "passive"))
    )
    (net (code "52") (name "unconnected-(U3-CTS-Pad9)") (class "Default")
      (node (ref "U3") (pin "9") (pinfunction "CTS_9") (pintype "passive"))
    )
    (net (code "53") (name "unconnected-(U3-DCD#-Pad12)") (class "Default")
      (node (ref "U3") (pin "12") (pinfunction "DCD#_12") (pintype "passive"))
    )
    (net (code "54") (name "unconnected-(U3-DSR#-Pad10)") (class "Default")
      (node (ref "U3") (pin "10") (pinfunction "DSR#_10") (pintype "passive"))
    )
    (net (code "55") (name "unconnected-(U3-R232-Pad15)") (class "Default")
      (node (ref "U3") (pin "15") (pinfunction "R232_15") (pintype "passive"))
    )
    (net (code "56") (name "unconnected-(U3-RI#-Pad11)") (class "Default")
      (node (ref "U3") (pin "11") (pinfunction "RI#_11") (pintype "passive"))
    )
    (net (code "57") (name "unconnected-(U3-RTS#-Pad14)") (class "Default")
      (node (ref "U3") (pin "14") (pinfunction "RTS#_14") (pintype "passive"))
    )
    (net (code "58") (name "unconnected-(X2-Pad4)") (class "Default")
      (node (ref "X2") (pin "4") (pintype "passive"))
    )
    (net (code "59") (name "unconnected-(ZU4-(ADC6)PC6-Pad19)") (class "Default")
      (node (ref "ZU4") (pin "19") (pinfunction "(ADC6)PC6_19") (pintype "passive"))
    )
    (net (code "60") (name "unconnected-(ZU4-(ADC7)PC7-Pad22)") (class "Default")
      (node (ref "ZU4") (pin "22") (pinfunction "(ADC7)PC7_22") (pintype "passive"))
    )
  )
)
